# fan5245-mk-1_0.net
KiCad netlist of a schematic drawn in EAGLE
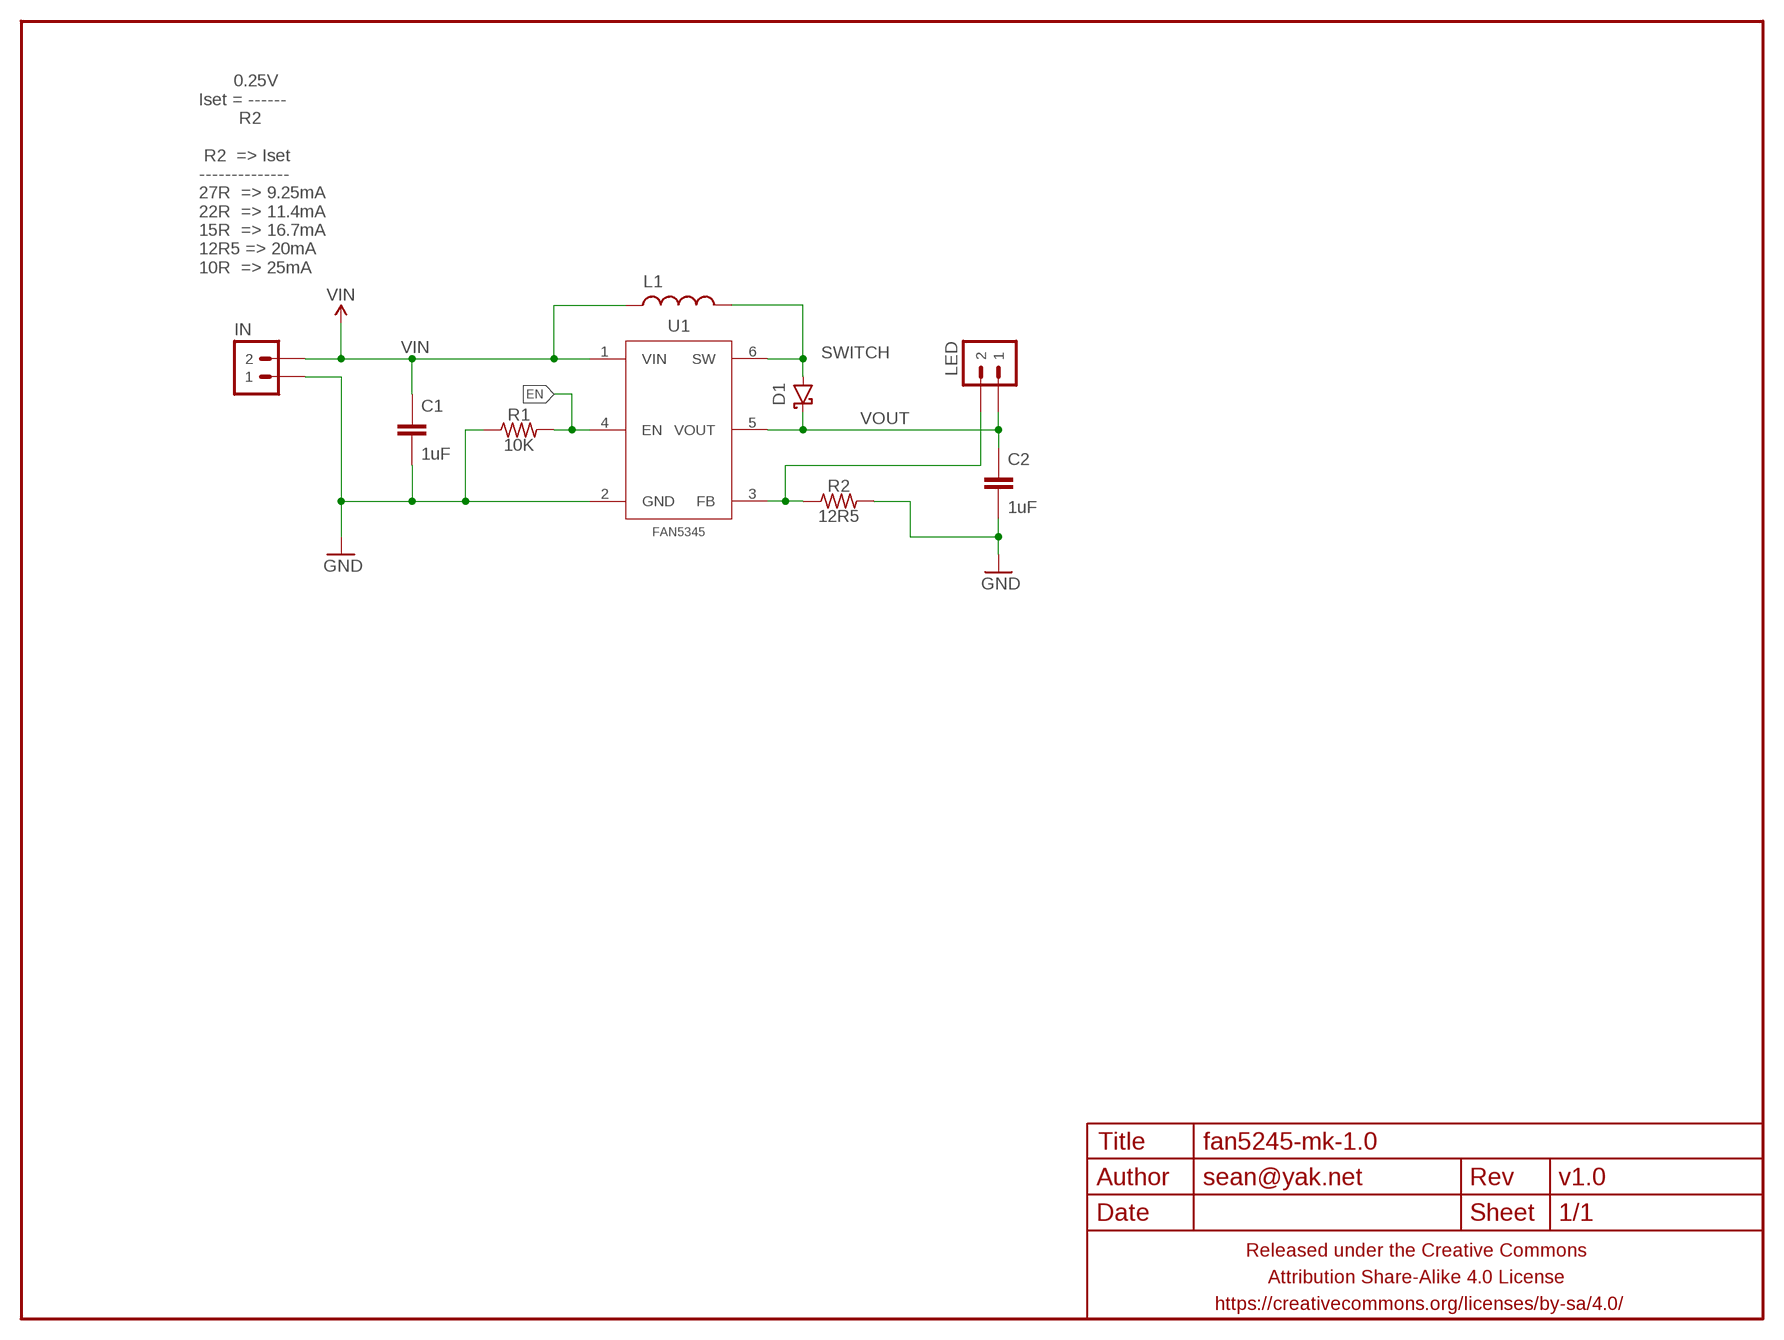
[diagram p0: schematic, sheet 1]

(export (version "E")
  (design (tool "Eeschema 10.0.6"))
  (components
    (comp (ref "C1")
      (value "1uF")
      (footprint "eagle-import:C0603-TIGHTER")
      (libsource (lib "eagle-import") (part "CAPACITOR-CERAMICC0603-TIGHTER"))
    )
    (comp (ref "C2")
      (value "1uF")
      (footprint "eagle-import:C0603-TIGHTER")
      (libsource (lib "eagle-import") (part "CAPACITOR-CERAMICC0603-TIGHTER"))
    )
    (comp (ref "D1")
      (value "DIODE-SCHOTTKYSOD323")
      (footprint "eagle-import:SOD323-SCHOTTKY")
      (libsource (lib "eagle-import") (part "DIODE-SCHOTTKYSOD323"))
    )
    (comp (ref "FRAME1")
      (value "FRAME-LETTERNO_PACKAGE")
      (footprint "eagle-import:DUMMY")
      (fields (field (name "DESIGNER") "sean@yak.net") (field (name "VERSION") "v1.0"))
      (libsource (lib "eagle-import") (part "FRAME-LETTERNO_PACKAGE"))
    )
    (comp (ref "IN")
      (value "M02PTH-CENTERED-R+")
      (footprint "eagle-import:1X02-CENTER-R+")
      (libsource (lib "eagle-import") (part "M02PTH-CENTERED-R+"))
    )
    (comp (ref "L1")
      (value "10uH")
      (footprint "eagle-import:L0603")
      (libsource (lib "eagle-import") (part "INDUCTOR0603-TIGHTER"))
    )
    (comp (ref "LED")
      (value "M02PTH-CENTERED-L+")
      (footprint "eagle-import:1X02-CENTER-L+")
      (libsource (lib "eagle-import") (part "M02PTH-CENTERED-L+"))
    )
    (comp (ref "R1")
      (value "10K")
      (footprint "eagle-import:R0603-TIGHTER")
      (libsource (lib "eagle-import") (part "RESISTORR0603-TIGHTER"))
    )
    (comp (ref "R2")
      (value "12R5")
      (footprint "eagle-import:R0603-TIGHTER")
      (libsource (lib "eagle-import") (part "RESISTORR0603-TIGHTER"))
    )
    (comp (ref "U1")
      (value "FAN5345")
      (footprint "eagle-import:SOT23-6")
      (libsource (lib "eagle-import") (part "FAN5345SSOT23"))
    )
  )
  (nets
    (net (code "1") (name "/SWITCH") (class "Default")
      (node (ref "D1") (pin "A") (pinfunction "A_A") (pintype "passive"))
      (node (ref "L1") (pin "2") (pinfunction "2_2") (pintype "passive"))
      (node (ref "U1") (pin "6") (pinfunction "SW_6") (pintype "bidirectional"))
    )
    (net (code "2") (name "/VOUT") (class "Default")
      (node (ref "C2") (pin "1") (pinfunction "1_1") (pintype "passive"))
      (node (ref "D1") (pin "C") (pinfunction "C_C") (pintype "passive"))
      (node (ref "LED") (pin "1") (pinfunction "1_1") (pintype "passive"))
      (node (ref "U1") (pin "5") (pinfunction "VOUT_5") (pintype "bidirectional"))
    )
    (net (code "3") (name "EN") (class "Default")
      (node (ref "R1") (pin "2") (pinfunction "2_2") (pintype "passive"))
      (node (ref "U1") (pin "4") (pinfunction "EN_4") (pintype "bidirectional"))
    )
    (net (code "4") (name "GND") (class "Default")
      (node (ref "C1") (pin "2") (pinfunction "2_2") (pintype "passive"))
      (node (ref "C2") (pin "2") (pinfunction "2_2") (pintype "passive"))
      (node (ref "IN") (pin "1") (pinfunction "1_1") (pintype "passive"))
      (node (ref "R1") (pin "1") (pinfunction "1_1") (pintype "passive"))
      (node (ref "R2") (pin "2") (pinfunction "2_2") (pintype "passive"))
      (node (ref "U1") (pin "2") (pinfunction "GND_2") (pintype "bidirectional"))
    )
    (net (code "5") (name "Net-(U1-FB)") (class "Default")
      (node (ref "LED") (pin "2") (pinfunction "2_2") (pintype "passive"))
      (node (ref "R2") (pin "1") (pinfunction "1_1") (pintype "passive"))
      (node (ref "U1") (pin "3") (pinfunction "FB_3") (pintype "bidirectional"))
    )
    (net (code "6") (name "VIN") (class "Default")
      (node (ref "C1") (pin "1") (pinfunction "1_1") (pintype "passive"))
      (node (ref "IN") (pin "2") (pinfunction "2_2") (pintype "passive"))
      (node (ref "L1") (pin "1") (pinfunction "1_1") (pintype "passive"))
      (node (ref "U1") (pin "1") (pinfunction "VIN_1") (pintype "bidirectional"))
    )
  )
)
